# jays-nfc-card-sch.net
KiCad netlist of a schematic drawn in EasyEDA
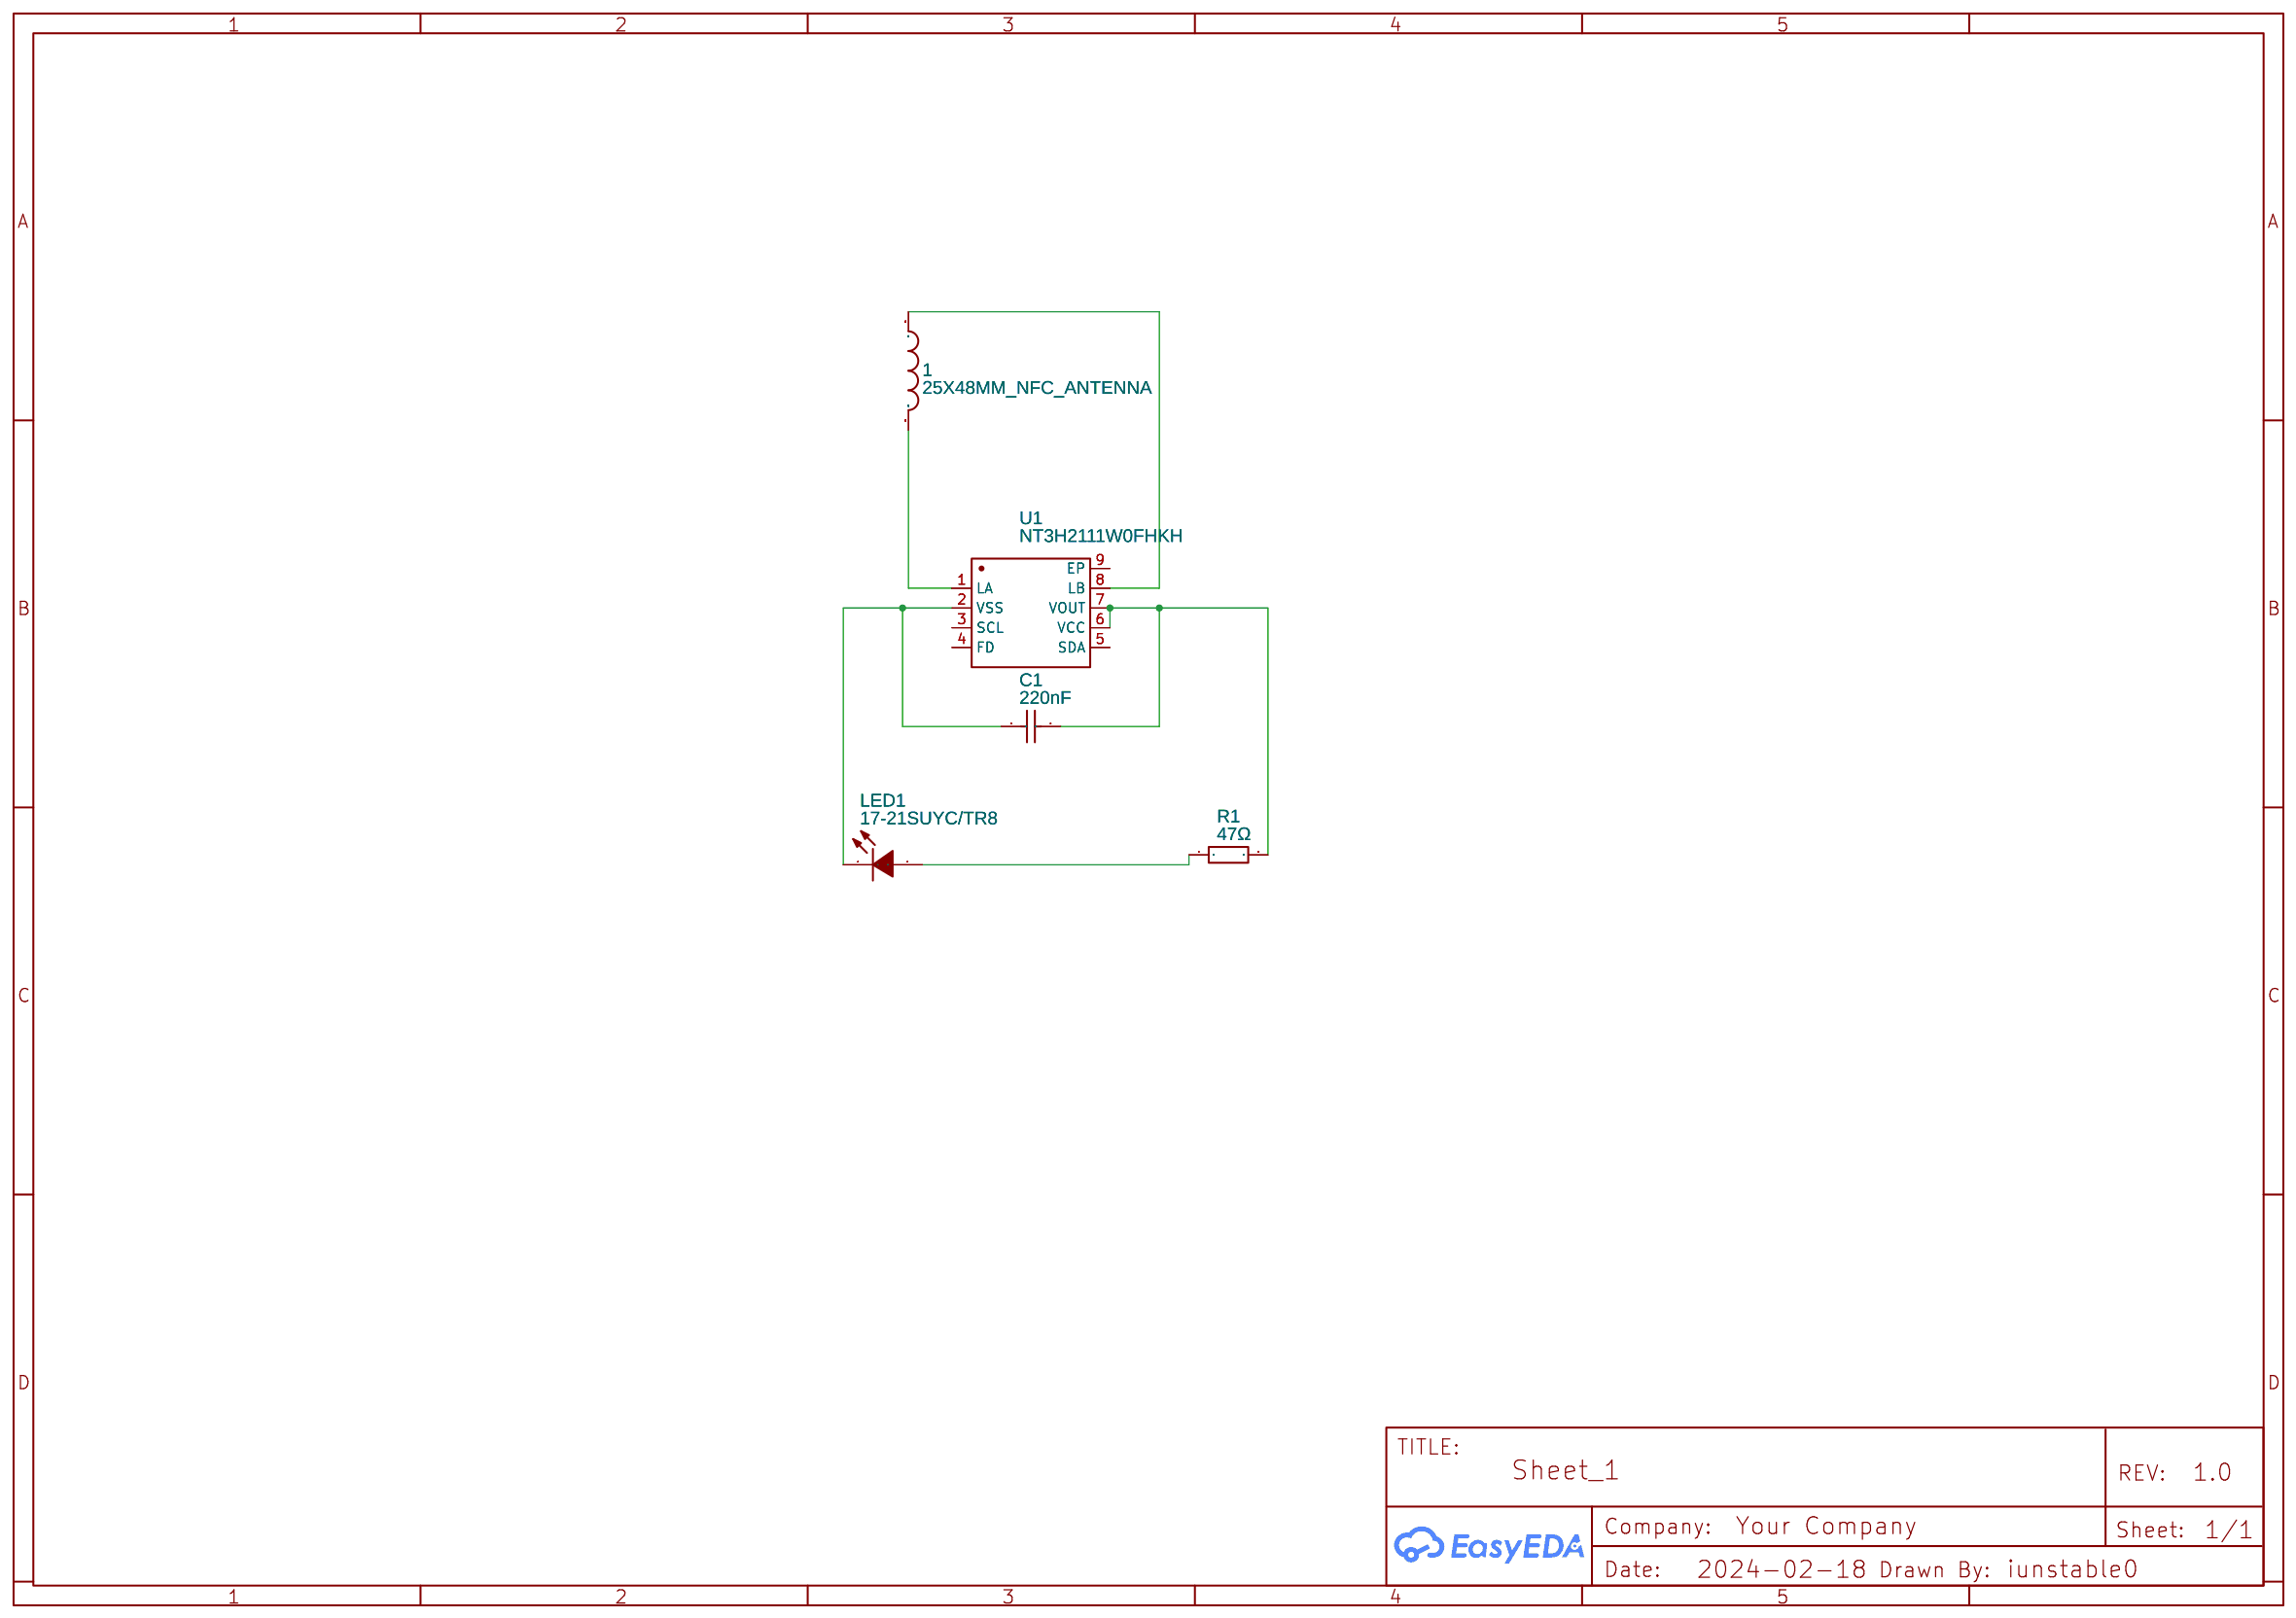
[diagram p0: schematic sheet]

(export (version "E")
  (design (tool "Eeschema 10.0.6"))
  (components
    (comp (ref "1") (value "25X48MM_NFC_ANTENNA") (libsource (lib "") (part "25X48MM_NFC_ANTENNA")))
    (comp (ref "C1")
      (value "220nF")
      (fields
        (field (name "Manufacturer Part") "CL10B224KA8NNNC")
        (field (name "Manufacturer") "SAMSUNG(三星)")
      )
      (libsource (lib "") (part "CL10B224KA8NNNC"))
    )
    (comp (ref "LED1")
      (value "17-21SUYC/TR8")
      (fields (field (name "Manufacturer Part") "KT-0805黄灯") (field (name "Manufacturer") "KENTO"))
      (libsource (lib "") (part "17-21SUYC/TR8"))
    )
    (comp (ref "R1")
      (value "47Ω")
      (fields
        (field (name "Manufacturer Part") "0603WAF470JT5E")
        (field (name "Manufacturer") "UNI-ROYAL(厚声)")
      )
      (libsource (lib "") (part "0603WAF470JT5E"))
    )
    (comp (ref "U1")
      (value "NT3H2111W0FHKH")
      (fields (field (name "Manufacturer") "NXP(恩智浦)"))
      (libsource (lib "") (part "NT3H2111W0FHKH"))
    )
  )
  (nets
    (net (code "1") (name "Net-(LED1-+)") (class "Default")
      (node (ref "LED1") (pin "1") (pinfunction "+_1") (pintype "unspecified"))
      (node (ref "R1") (pin "1") (pinfunction "1_1") (pintype "input"))
    )
    (net (code "2") (name "Net-(LED1--)") (class "Default")
      (node (ref "C1") (pin "1") (pinfunction "1_1") (pintype "input"))
      (node (ref "LED1") (pin "2") (pinfunction "-_2") (pintype "unspecified"))
      (node (ref "U1") (pin "2") (pinfunction "VSS_2") (pintype "unspecified"))
    )
    (net (code "3") (name "Net-(U1-LA)") (class "Default")
      (node (ref "1") (pin "P$2") (pinfunction "P$2_P$2") (pintype "bidirectional"))
      (node (ref "U1") (pin "1") (pinfunction "LA_1") (pintype "unspecified"))
    )
    (net (code "4") (name "Net-(U1-LB)") (class "Default")
      (node (ref "1") (pin "P$1") (pinfunction "P$1_P$1") (pintype "bidirectional"))
      (node (ref "U1") (pin "8") (pinfunction "LB_8") (pintype "unspecified"))
    )
    (net (code "5") (name "Net-(U1-VCC)") (class "Default")
      (node (ref "C1") (pin "2") (pinfunction "2_2") (pintype "input"))
      (node (ref "R1") (pin "2") (pinfunction "2_2") (pintype "input"))
      (node (ref "U1") (pin "6") (pinfunction "VCC_6") (pintype "unspecified"))
      (node (ref "U1") (pin "7") (pinfunction "VOUT_7") (pintype "unspecified"))
    )
    (net (code "6") (name "unconnected-(U1-EP-Pad9)") (class "Default")
      (node (ref "U1") (pin "9") (pinfunction "EP_9") (pintype "unspecified"))
    )
    (net (code "7") (name "unconnected-(U1-FD-Pad4)") (class "Default")
      (node (ref "U1") (pin "4") (pinfunction "FD_4") (pintype "unspecified"))
    )
    (net (code "8") (name "unconnected-(U1-SCL-Pad3)") (class "Default")
      (node (ref "U1") (pin "3") (pinfunction "SCL_3") (pintype "unspecified"))
    )
    (net (code "9") (name "unconnected-(U1-SDA-Pad5)") (class "Default")
      (node (ref "U1") (pin "5") (pinfunction "SDA_5") (pintype "unspecified"))
    )
  )
)
